# STM32.net
KiCad netlist of a schematic drawn in Altium Designer
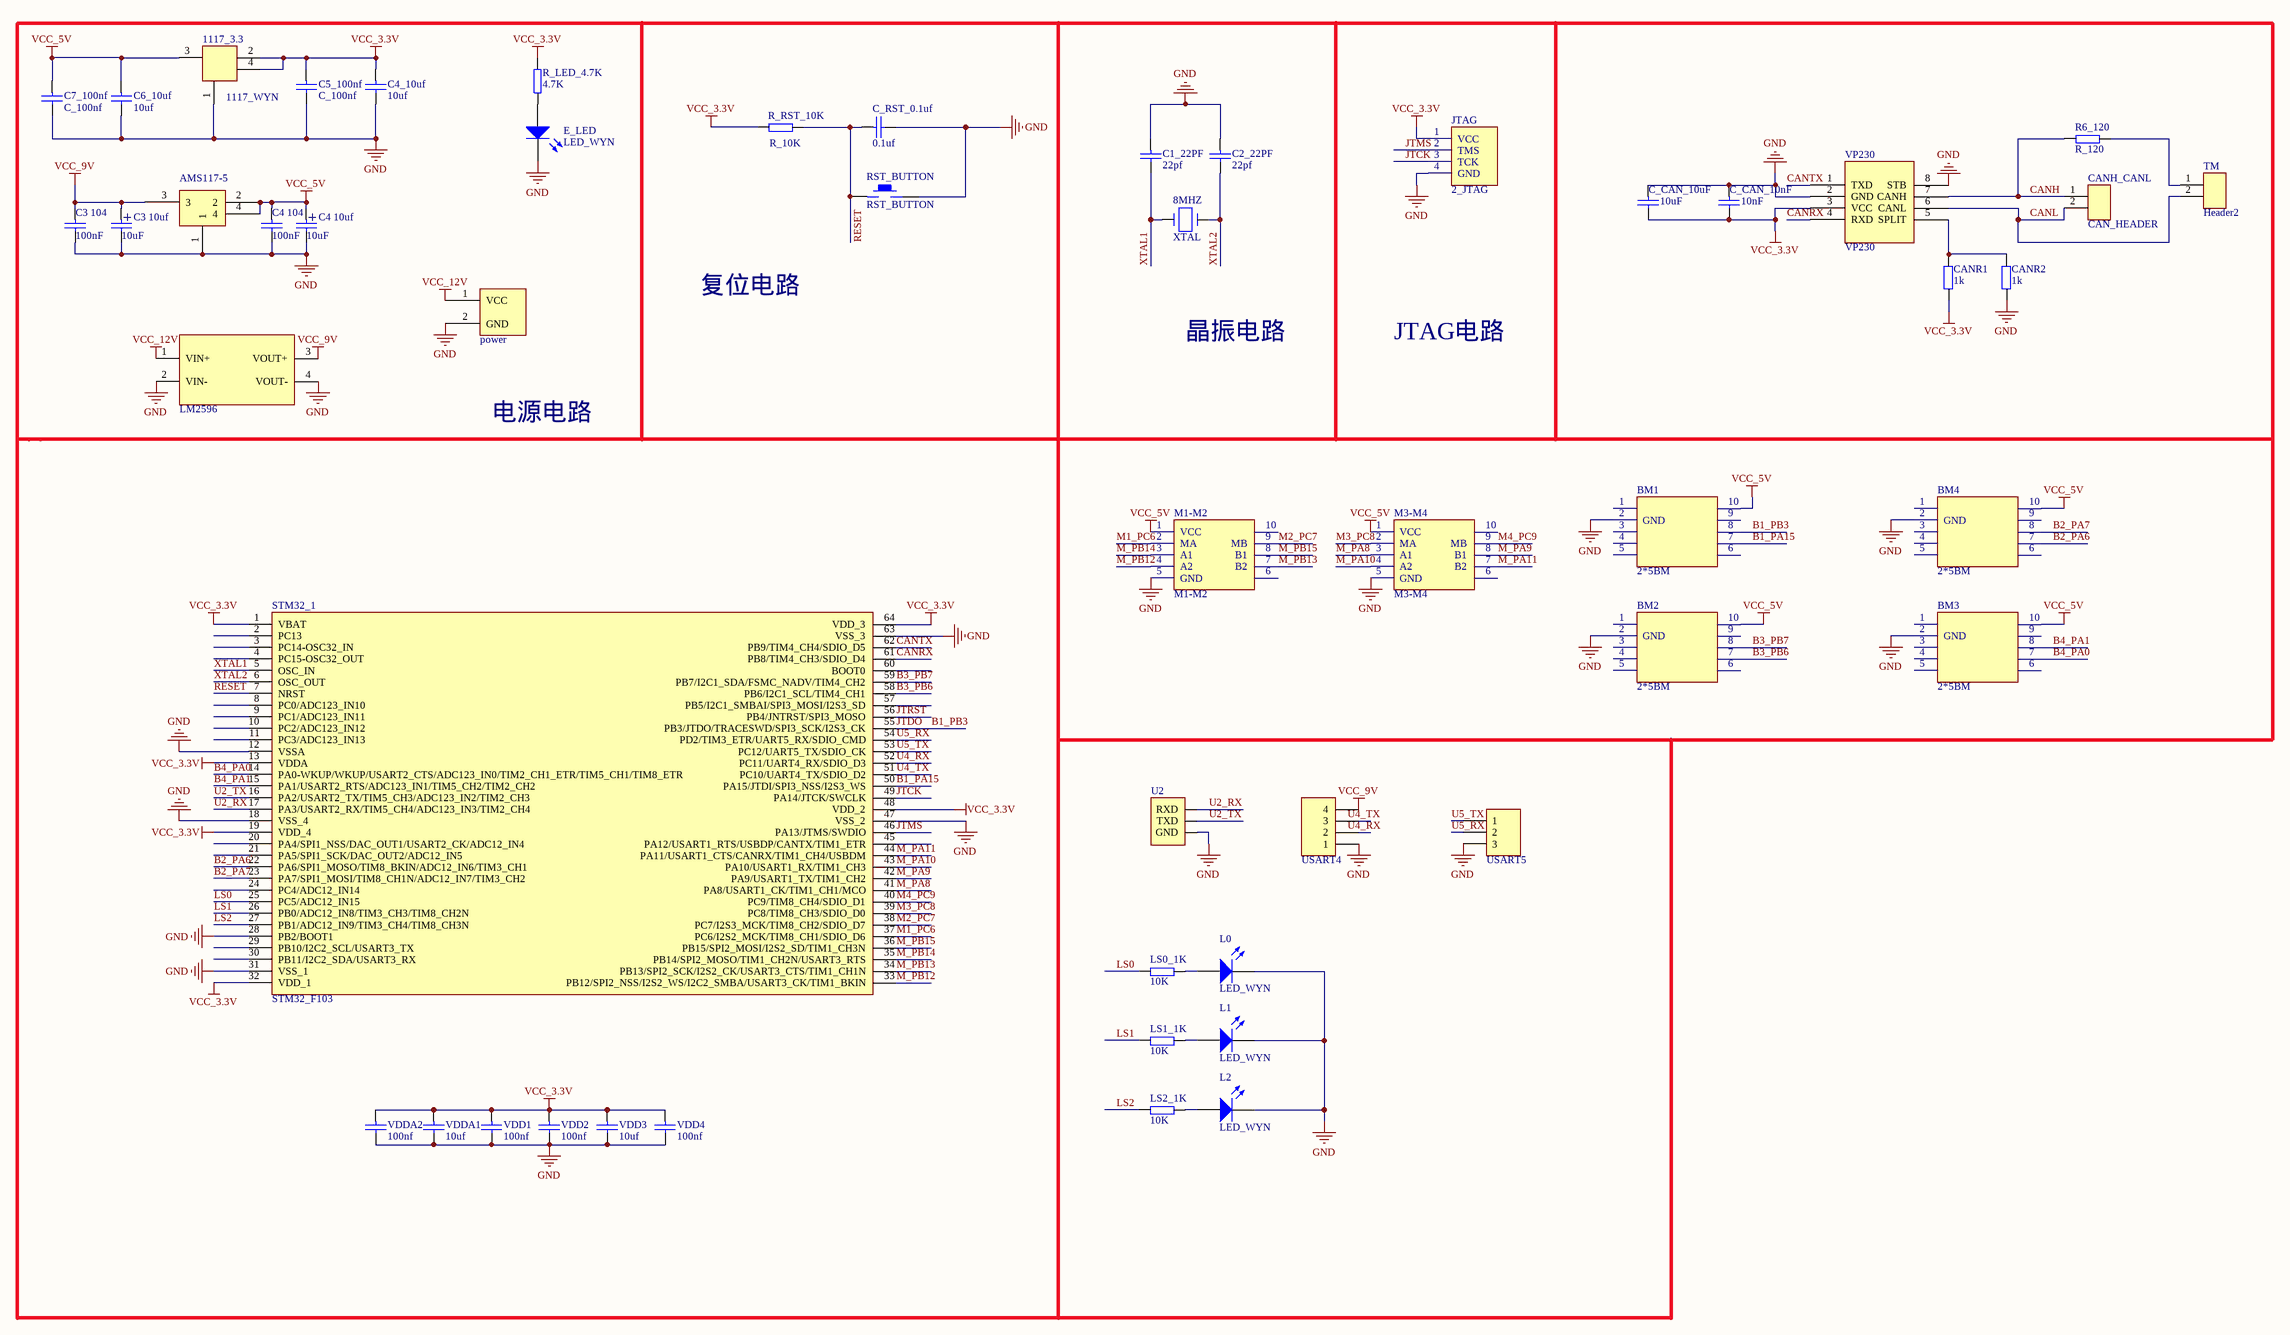
[diagram p0: STM32电机.SchDoc]

(export (version "E")
  (design (tool "Eeschema 10.0.6"))
  (components
    (comp (ref "8MHZ") (value "XTAL") (footprint "XTAL_D") (libsource (lib "STM32主处理板") (part "XTAL")))
    (comp (ref "1117_3.3")
      (value "1117_WYN")
      (footprint "SOT-223_WYN")
      (libsource (lib "STM32主处理板") (part "1117_WYN"))
    )
    (comp (ref "AMS117-5")
      (value "1117-3.3")
      (footprint "SOT-223_WYN")
      (libsource (lib "main") (part "1117_WYN"))
    )
    (comp (ref "BM1") (value "2*5BM") (footprint "JTAG_10to20") (libsource (lib "STM32主处理板") (part "2*5BM")))
    (comp (ref "BM2") (value "2*5BM") (footprint "JTAG_10to20") (libsource (lib "STM32主处理板") (part "2*5BM")))
    (comp (ref "BM3") (value "2*5BM") (footprint "JTAG_10to20") (libsource (lib "STM32主处理板") (part "2*5BM")))
    (comp (ref "BM4") (value "2*5BM") (footprint "JTAG_10to20") (libsource (lib "STM32主处理板") (part "2*5BM")))
    (comp (ref "C1_22PF")
      (value "22pf")
      (footprint "0603_WYH")
      (libsource (lib "STM32主处理板") (part "CAP_WYN"))
    )
    (comp (ref "C2_22PF")
      (value "22pf")
      (footprint "0603_WYH")
      (libsource (lib "STM32主处理板") (part "CAP_WYN"))
    )
    (comp (ref "C3 10uf") (value "10uF") (footprint "0603_WYH") (libsource (lib "main") (part "CAP_POL_WYN")))
    (comp (ref "C3 104") (value "100nF") (footprint "0603_WYH") (libsource (lib "main") (part "CAP_WYN")))
    (comp (ref "C4 10uf") (value "10uF") (footprint "0603_WYH") (libsource (lib "main") (part "CAP_POL_WYN")))
    (comp (ref "C4 104") (value "100nF") (footprint "0603_WYH") (libsource (lib "main") (part "CAP_WYN")))
    (comp (ref "C4_10uf")
      (value "10uf")
      (footprint "0603_WYH")
      (libsource (lib "STM32主处理板") (part "CAP_WYN"))
    )
    (comp (ref "C5_100nf")
      (value "C_100nf")
      (footprint "0603_WYH")
      (libsource (lib "STM32主处理板") (part "CAP_WYN"))
    )
    (comp (ref "C6_10uf")
      (value "10uf")
      (footprint "0603_WYH")
      (libsource (lib "STM32主处理板") (part "CAP_WYN"))
    )
    (comp (ref "C7_100nf")
      (value "C_100nf")
      (footprint "0603_WYH")
      (libsource (lib "STM32主处理板") (part "CAP_WYN"))
    )
    (comp (ref "CANH_CANL")
      (value "CAN_HEADER")
      (footprint "CAN信号")
      (libsource (lib "STM32主处理板") (part "CAN_HEADER"))
    )
    (comp (ref "CANR1") (value "1k") (footprint "0603_WYH") (libsource (lib "战舰STM32开发板底板封装库") (part "R")))
    (comp (ref "CANR2") (value "1k") (footprint "0603_WYH") (libsource (lib "战舰STM32开发板底板封装库") (part "R")))
    (comp (ref "C_CAN_10nF")
      (value "10nF")
      (footprint "0603_WYH")
      (libsource (lib "STM32主处理板") (part "CAP_WYN"))
    )
    (comp (ref "C_CAN_10uF")
      (value "10uF")
      (footprint "0603_WYH")
      (libsource (lib "STM32主处理板") (part "CAP_WYN"))
    )
    (comp (ref "C_RST_0.1uf")
      (value "0.1uf")
      (footprint "0603_WYH")
      (libsource (lib "STM32主处理板") (part "CAP_WYN"))
    )
    (comp (ref "E_LED")
      (value "LED_WYN")
      (footprint "0603_WYH")
      (libsource (lib "STM32主处理板") (part "LED_WYN"))
    )
    (comp (ref "JTAG") (value "2_JTAG") (footprint "2_JTAG") (libsource (lib "STM32主处理板") (part "2_JTAG")))
    (comp (ref "L0") (value "LED_WYN") (footprint "0603_WYH") (libsource (lib "STM32主处理板") (part "LED_WYN")))
    (comp (ref "L1") (value "LED_WYN") (footprint "0603_WYH") (libsource (lib "STM32主处理板") (part "LED_WYN")))
    (comp (ref "L2") (value "LED_WYN") (footprint "0603_WYH") (libsource (lib "STM32主处理板") (part "LED_WYN")))
    (comp (ref "LM2596") (value "LM2596") (footprint "LM2596") (libsource (lib "救援2") (part "LM2596")))
    (comp (ref "LS0_1K") (value "10K") (footprint "0603_WYH") (libsource (lib "战舰STM32开发板底板封装库") (part "R")))
    (comp (ref "LS1_1K") (value "10K") (footprint "0603_WYH") (libsource (lib "战舰STM32开发板底板封装库") (part "R")))
    (comp (ref "LS2_1K") (value "10K") (footprint "0603_WYH") (libsource (lib "战舰STM32开发板底板封装库") (part "R")))
    (comp (ref "M1-M2") (value "M1-M2") (footprint "JTAG_10to20") (libsource (lib "STM32主处理板") (part "电机接口")))
    (comp (ref "M3-M4") (value "M3-M4") (footprint "JTAG_10to20") (libsource (lib "STM32主处理板") (part "电机接口")))
    (comp (ref "POWER") (value "power") (footprint "power") (libsource (lib "救援1") (part "power")))
    (comp (ref "R6_120")
      (value "R_120")
      (footprint "0603_WYH")
      (libsource (lib "战舰STM32开发板底板封装库") (part "R"))
    )
    (comp (ref "RST_BUTTON")
      (value "RST_BUTTON")
      (footprint "CLCK")
      (libsource (lib "STM32主处理板") (part "RST_BUTTON"))
    )
    (comp (ref "R_LED_4.7K")
      (value "4.7K")
      (footprint "0603_WYH")
      (libsource (lib "STM32主处理板") (part "RES_WYN"))
    )
    (comp (ref "R_RST_10K")
      (value "R_10K")
      (footprint "0603_WYH")
      (libsource (lib "战舰STM32开发板底板封装库") (part "R"))
    )
    (comp (ref "STM32_1")
      (value "STM32_F103")
      (footprint "STM32TSQFP50P1200X1200X160-64N")
      (libsource (lib "STM32主处理板") (part "STM32_F103"))
    )
    (comp (ref "TM") (value "Header2") (footprint "HDR1X2") (libsource (lib "STM32主处理板") (part "Header2")))
    (comp (ref "U2") (value "三针串口") (footprint "HDR1X3") (libsource (lib "STM32主处理板") (part "三针串口")))
    (comp (ref "USART4") (value "Header-4") (footprint "HDR1X4") (libsource (lib "救援1") (part "Header-4")))
    (comp (ref "USART5") (value "Header-3") (footprint "HDR1X3") (libsource (lib "救援1") (part "Header-3")))
    (comp (ref "VDD1") (value "100nf") (footprint "0603_WYH") (libsource (lib "STM32主处理板") (part "CAP_WYN")))
    (comp (ref "VDD2") (value "100nf") (footprint "0603_WYH") (libsource (lib "STM32主处理板") (part "CAP_WYN")))
    (comp (ref "VDD3") (value "10uf") (footprint "0603_WYH") (libsource (lib "STM32主处理板") (part "CAP_WYN")))
    (comp (ref "VDD4") (value "100nf") (footprint "0603_WYH") (libsource (lib "STM32主处理板") (part "CAP_WYN")))
    (comp (ref "VDDA1") (value "10uf") (footprint "0603_WYH") (libsource (lib "STM32主处理板") (part "CAP_WYN")))
    (comp (ref "VDDA2") (value "100nf") (footprint "0603_WYH") (libsource (lib "STM32主处理板") (part "CAP_WYN")))
    (comp (ref "VP230") (value "VP230") (footprint "VP230") (libsource (lib "STM32主处理板") (part "VP230")))
  )
  (nets
    (net (code "1") (name "/B1_PA15") (class "Default")
      (node (ref "BM1") (pin "7") (pintype "passive"))
      (node (ref "STM32_1") (pin "50") (pinfunction "PA15/JTDI/SPI3_NSS/I2S3_WS_50") (pintype "passive"))
    )
    (net (code "2") (name "/B1_PB3") (class "Default")
      (node (ref "BM1") (pin "8") (pintype "passive"))
      (node (ref "STM32_1") (pin "55") (pinfunction "PB3/JTDO/TRACESWD/SPI3_SCK/I2S3_CK_55") (pintype "passive"))
    )
    (net (code "3") (name "/B2_PA6") (class "Default")
      (node (ref "BM4") (pin "7") (pintype "passive"))
      (node (ref "STM32_1") (pin "22") (pinfunction "PA6/SPI1_MOSO/TIM8_BKIN/ADC12_IN6/TIM3_CH1_22") (pintype "passive"))
    )
    (net (code "4") (name "/B2_PA7") (class "Default")
      (node (ref "BM4") (pin "8") (pintype "passive"))
      (node (ref "STM32_1") (pin "23") (pinfunction "PA7/SPI1_MOSI/TIM8_CH1N/ADC12_IN7/TIM3_CH2_23") (pintype "passive"))
    )
    (net (code "5") (name "/B3_PB6") (class "Default")
      (node (ref "BM2") (pin "7") (pintype "passive"))
      (node (ref "STM32_1") (pin "58") (pinfunction "PB6/I2C1_SCL/TIM4_CH1_58") (pintype "passive"))
    )
    (net (code "6") (name "/B3_PB7") (class "Default")
      (node (ref "BM2") (pin "8") (pintype "passive"))
      (node (ref "STM32_1") (pin "59") (pinfunction "PB7/I2C1_SDA/FSMC_NADV/TIM4_CH2_59") (pintype "passive"))
    )
    (net (code "7") (name "/B4_PA0") (class "Default")
      (node (ref "BM3") (pin "7") (pintype "passive"))
      (node (ref "STM32_1") (pin "14") (pinfunction "PA0-WKUP/WKUP/USART2_CTS/ADC123_IN0/TIM2_CH1_ETR/TIM5_CH1/TIM8_ETR_14") (pintype "passive"))
    )
    (net (code "8") (name "/B4_PA1") (class "Default")
      (node (ref "BM3") (pin "8") (pintype "passive"))
      (node (ref "STM32_1") (pin "15") (pinfunction "PA1/USART2_RTS/ADC123_IN1/TIM5_CH2/TIM2_CH2_15") (pintype "passive"))
    )
    (net (code "9") (name "/CANH") (class "Default")
      (node (ref "CANH_CANL") (pin "1") (pintype "passive"))
      (node (ref "R6_120") (pin "1") (pintype "passive"))
      (node (ref "VP230") (pin "7") (pinfunction "CANH_7") (pintype "passive"))
    )
    (net (code "10") (name "/CANL") (class "Default")
      (node (ref "CANH_CANL") (pin "2") (pintype "passive"))
      (node (ref "TM") (pin "2") (pintype "passive"))
      (node (ref "VP230") (pin "6") (pinfunction "CANL_6") (pintype "passive"))
    )
    (net (code "11") (name "/CANRX") (class "Default")
      (node (ref "STM32_1") (pin "61") (pinfunction "PB8/TIM4_CH3/SDIO_D4_61") (pintype "passive"))
      (node (ref "VP230") (pin "4") (pinfunction "RXD_4") (pintype "passive"))
    )
    (net (code "12") (name "/CANTX") (class "Default")
      (node (ref "STM32_1") (pin "62") (pinfunction "PB9/TIM4_CH4/SDIO_D5_62") (pintype "passive"))
      (node (ref "VP230") (pin "1") (pinfunction "TXD_1") (pintype "passive"))
    )
    (net (code "13") (name "/JTCK") (class "Default")
      (node (ref "JTAG") (pin "3") (pinfunction "TCK_3") (pintype "passive"))
      (node (ref "STM32_1") (pin "49") (pinfunction "PA14/JTCK/SWCLK_49") (pintype "passive"))
    )
    (net (code "14") (name "/JTMS") (class "Default")
      (node (ref "JTAG") (pin "2") (pinfunction "TMS_2") (pintype "passive"))
      (node (ref "STM32_1") (pin "46") (pinfunction "PA13/JTMS/SWDIO_46") (pintype "passive"))
    )
    (net (code "15") (name "/JTRST") (class "Default")
      (node (ref "STM32_1") (pin "56") (pinfunction "PB4/JNTRST/SPI3_MOSO_56") (pintype "passive"))
    )
    (net (code "16") (name "/LS0") (class "Default")
      (node (ref "LS0_1K") (pin "1") (pintype "passive"))
      (node (ref "STM32_1") (pin "25") (pinfunction "PC5/ADC12_IN15_25") (pintype "passive"))
    )
    (net (code "17") (name "/LS1") (class "Default")
      (node (ref "LS1_1K") (pin "1") (pintype "passive"))
      (node (ref "STM32_1") (pin "26") (pinfunction "PB0/ADC12_IN8/TIM3_CH3/TIM8_CH2N_26") (pintype "passive"))
    )
    (net (code "18") (name "/LS2") (class "Default")
      (node (ref "LS2_1K") (pin "1") (pintype "passive"))
      (node (ref "STM32_1") (pin "27") (pinfunction "PB1/ADC12_IN9/TIM3_CH4/TIM8_CH3N_27") (pintype "passive"))
    )
    (net (code "19") (name "/M1_PC6") (class "Default")
      (node (ref "M1-M2") (pin "2") (pinfunction "MA_2") (pintype "passive"))
      (node (ref "STM32_1") (pin "37") (pinfunction "PC6/I2S2_MCK/TIM8_CH1/SDIO_D6_37") (pintype "passive"))
    )
    (net (code "20") (name "/M2_PC7") (class "Default")
      (node (ref "M1-M2") (pin "9") (pinfunction "MB_9") (pintype "passive"))
      (node (ref "STM32_1") (pin "38") (pinfunction "PC7/I2S3_MCK/TIM8_CH2/SDIO_D7_38") (pintype "passive"))
    )
    (net (code "21") (name "/M3_PC8") (class "Default")
      (node (ref "M3-M4") (pin "2") (pinfunction "MA_2") (pintype "passive"))
      (node (ref "STM32_1") (pin "39") (pinfunction "PC8/TIM8_CH3/SDIO_D0_39") (pintype "passive"))
    )
    (net (code "22") (name "/M4_PC9") (class "Default")
      (node (ref "M3-M4") (pin "9") (pinfunction "MB_9") (pintype "passive"))
      (node (ref "STM32_1") (pin "40") (pinfunction "PC9/TIM8_CH4/SDIO_D1_40") (pintype "passive"))
    )
    (net (code "23") (name "/M_PA8") (class "Default")
      (node (ref "M3-M4") (pin "3") (pinfunction "A1_3") (pintype "passive"))
      (node (ref "STM32_1") (pin "41") (pinfunction "PA8/USART1_CK/TIM1_CH1/MCO_41") (pintype "passive"))
    )
    (net (code "24") (name "/M_PA9") (class "Default")
      (node (ref "M3-M4") (pin "8") (pinfunction "B1_8") (pintype "passive"))
      (node (ref "STM32_1") (pin "42") (pinfunction "PA9/USART1_TX/TIM1_CH2_42") (pintype "passive"))
    )
    (net (code "25") (name "/M_PA10") (class "Default")
      (node (ref "M3-M4") (pin "4") (pinfunction "A2_4") (pintype "passive"))
      (node (ref "STM32_1") (pin "43") (pinfunction "PA10/USART1_RX/TIM1_CH3_43") (pintype "passive"))
    )
    (net (code "26") (name "/M_PA11") (class "Default")
      (node (ref "M3-M4") (pin "7") (pinfunction "B2_7") (pintype "passive"))
      (node (ref "STM32_1") (pin "44") (pinfunction "PA11/USART1_CTS/CANRX/TIM1_CH4/USBDM_44") (pintype "passive"))
    )
    (net (code "27") (name "/M_PB12") (class "Default")
      (node (ref "M1-M2") (pin "4") (pinfunction "A2_4") (pintype "passive"))
      (node (ref "STM32_1") (pin "33") (pinfunction "PB12/SPI2_NSS/I2S2_WS/I2C2_SMBA/USART3_CK/TIM1_BKIN_33") (pintype "passive"))
    )
    (net (code "28") (name "/M_PB13") (class "Default")
      (node (ref "M1-M2") (pin "7") (pinfunction "B2_7") (pintype "passive"))
      (node (ref "STM32_1") (pin "34") (pinfunction "PB13/SPI2_SCK/I2S2_CK/USART3_CTS/TIM1_CH1N_34") (pintype "passive"))
    )
    (net (code "29") (name "/M_PB14") (class "Default")
      (node (ref "M1-M2") (pin "3") (pinfunction "A1_3") (pintype "passive"))
      (node (ref "STM32_1") (pin "35") (pinfunction "PB14/SPI2_MOSO/TIM1_CH2N/USART3_RTS_35") (pintype "passive"))
    )
    (net (code "30") (name "/M_PB15") (class "Default")
      (node (ref "M1-M2") (pin "8") (pinfunction "B1_8") (pintype "passive"))
      (node (ref "STM32_1") (pin "36") (pinfunction "PB15/SPI2_MOSI/I2S2_SD/TIM1_CH3N_36") (pintype "passive"))
    )
    (net (code "31") (name "/RESET") (class "Default")
      (node (ref "C_RST_0.1uf") (pin "1") (pintype "passive"))
      (node (ref "RST_BUTTON") (pin "1") (pinfunction "1_1") (pintype "passive"))
      (node (ref "R_RST_10K") (pin "2") (pintype "passive"))
      (node (ref "STM32_1") (pin "7") (pinfunction "NRST_7") (pintype "passive"))
    )
    (net (code "32") (name "/U2_RX") (class "Default")
      (node (ref "STM32_1") (pin "17") (pinfunction "PA3/USART2_RX/TIM5_CH4/ADC123_IN3/TIM2_CH4_17") (pintype "passive"))
      (node (ref "U2") (pin "1") (pinfunction "RXD_1") (pintype "passive"))
    )
    (net (code "33") (name "/U2_TX") (class "Default")
      (node (ref "STM32_1") (pin "16") (pinfunction "PA2/USART2_TX/TIM5_CH3/ADC123_IN2/TIM2_CH3_16") (pintype "passive"))
      (node (ref "U2") (pin "2") (pinfunction "TXD_2") (pintype "passive"))
    )
    (net (code "34") (name "/U4_RX") (class "Default")
      (node (ref "STM32_1") (pin "52") (pinfunction "PC11/UART4_RX/SDIO_D3_52") (pintype "passive"))
    )
    (net (code "35") (name "/U4_TX") (class "Default")
      (node (ref "STM32_1") (pin "51") (pinfunction "PC10/UART4_TX/SDIO_D2_51") (pintype "passive"))
    )
    (net (code "36") (name "/U5_RX") (class "Default")
      (node (ref "STM32_1") (pin "54") (pinfunction "PD2/TIM3_ETR/UART5_RX/SDIO_CMD_54") (pintype "passive"))
      (node (ref "USART5") (pin "2") (pinfunction "2_2") (pintype "passive"))
    )
    (net (code "37") (name "/U5_TX") (class "Default")
      (node (ref "STM32_1") (pin "53") (pinfunction "PC12/UART5_TX/SDIO_CK_53") (pintype "passive"))
      (node (ref "USART5") (pin "1") (pinfunction "1_1") (pintype "passive"))
    )
    (net (code "38") (name "/XTAL1") (class "Default")
      (node (ref "8MHZ") (pin "1") (pinfunction "1_1") (pintype "passive"))
      (node (ref "C1_22PF") (pin "2") (pintype "passive"))
      (node (ref "STM32_1") (pin "5") (pinfunction "OSC_IN_5") (pintype "passive"))
    )
    (net (code "39") (name "/XTAL2") (class "Default")
      (node (ref "8MHZ") (pin "2") (pinfunction "2_2") (pintype "passive"))
      (node (ref "C2_22PF") (pin "2") (pintype "passive"))
      (node (ref "STM32_1") (pin "6") (pinfunction "OSC_OUT_6") (pintype "passive"))
    )
    (net (code "40") (name "GND") (class "Default")
      (node (ref "1117_3.3") (pin "1") (pintype "passive"))
      (node (ref "AMS117-5") (pin "1") (pinfunction "1_1") (pintype "passive"))
      (node (ref "BM1") (pin "2") (pinfunction "GND_2") (pintype "passive"))
      (node (ref "BM2") (pin "2") (pinfunction "GND_2") (pintype "passive"))
      (node (ref "BM3") (pin "2") (pinfunction "GND_2") (pintype "passive"))
      (node (ref "BM4") (pin "2") (pinfunction "GND_2") (pintype "passive"))
      (node (ref "C1_22PF") (pin "1") (pintype "passive"))
      (node (ref "C2_22PF") (pin "1") (pintype "passive"))
      (node (ref "C3 104") (pin "2") (pintype "passive"))
      (node (ref "C3 10uf") (pin "2") (pintype "passive"))
      (node (ref "C4 104") (pin "2") (pintype "passive"))
      (node (ref "C4 10uf") (pin "2") (pintype "passive"))
      (node (ref "C4_10uf") (pin "2") (pintype "passive"))
      (node (ref "C5_100nf") (pin "2") (pintype "passive"))
      (node (ref "C6_10uf") (pin "2") (pintype "passive"))
      (node (ref "C7_100nf") (pin "2") (pintype "passive"))
      (node (ref "CANR2") (pin "2") (pintype "passive"))
      (node (ref "C_CAN_10nF") (pin "1") (pintype "passive"))
      (node (ref "C_CAN_10uF") (pin "1") (pintype "passive"))
      (node (ref "C_RST_0.1uf") (pin "2") (pintype "passive"))
      (node (ref "E_LED") (pin "2") (pinfunction "K_2") (pintype "passive"))
      (node (ref "JTAG") (pin "4") (pinfunction "GND_4") (pintype "passive"))
      (node (ref "L0") (pin "2") (pinfunction "K_2") (pintype "passive"))
      (node (ref "L1") (pin "2") (pinfunction "K_2") (pintype "passive"))
      (node (ref "L2") (pin "2") (pinfunction "K_2") (pintype "passive"))
      (node (ref "LM2596") (pin "2") (pinfunction "VIN-_2") (pintype "passive"))
      (node (ref "LM2596") (pin "4") (pinfunction "VOUT-_4") (pintype "passive"))
      (node (ref "M1-M2") (pin "5") (pinfunction "GND_5") (pintype "passive"))
      (node (ref "M3-M4") (pin "5") (pinfunction "GND_5") (pintype "passive"))
      (node (ref "POWER") (pin "2") (pinfunction "GND_2") (pintype "passive"))
      (node (ref "RST_BUTTON") (pin "2") (pinfunction "2_2") (pintype "passive"))
      (node (ref "STM32_1") (pin "12") (pinfunction "VSSA_12") (pintype "passive"))
      (node (ref "STM32_1") (pin "18") (pinfunction "VSS_4_18") (pintype "passive"))
      (node (ref "STM32_1") (pin "28") (pinfunction "PB2/BOOT1_28") (pintype "passive"))
      (node (ref "STM32_1") (pin "31") (pinfunction "VSS_1_31") (pintype "passive"))
      (node (ref "STM32_1") (pin "47") (pinfunction "VSS_2_47") (pintype "passive"))
      (node (ref "STM32_1") (pin "63") (pinfunction "VSS_3_63") (pintype "passive"))
      (node (ref "U2") (pin "3") (pinfunction "GND_3") (pintype "passive"))
      (node (ref "USART4") (pin "1") (pinfunction "1_1") (pintype "passive"))
      (node (ref "USART5") (pin "3") (pinfunction "3_3") (pintype "passive"))
      (node (ref "VDD1") (pin "2") (pintype "passive"))
      (node (ref "VDD2") (pin "2") (pintype "passive"))
      (node (ref "VDD3") (pin "2") (pintype "passive"))
      (node (ref "VDD4") (pin "2") (pintype "passive"))
      (node (ref "VDDA1") (pin "2") (pintype "passive"))
      (node (ref "VDDA2") (pin "2") (pintype "passive"))
      (node (ref "VP230") (pin "2") (pinfunction "GND_2") (pintype "passive"))
      (node (ref "VP230") (pin "8") (pinfunction "STB_8") (pintype "passive"))
    )
    (net (code "41") (name "Net-(E_LED-A)") (class "Default")
      (node (ref "E_LED") (pin "1") (pinfunction "A_1") (pintype "passive"))
      (node (ref "R_LED_4.7K") (pin "1") (pinfunction "1_1") (pintype "passive"))
    )
    (net (code "42") (name "Net-(L0-A)") (class "Default")
      (node (ref "L0") (pin "1") (pinfunction "A_1") (pintype "passive"))
      (node (ref "LS0_1K") (pin "2") (pintype "passive"))
    )
    (net (code "43") (name "Net-(L1-A)") (class "Default")
      (node (ref "L1") (pin "1") (pinfunction "A_1") (pintype "passive"))
      (node (ref "LS1_1K") (pin "2") (pintype "passive"))
    )
    (net (code "44") (name "Net-(L2-A)") (class "Default")
      (node (ref "L2") (pin "1") (pinfunction "A_1") (pintype "passive"))
      (node (ref "LS2_1K") (pin "2") (pintype "passive"))
    )
    (net (code "45") (name "Net-(R6_120-Pad2)") (class "Default")
      (node (ref "R6_120") (pin "2") (pintype "passive"))
      (node (ref "TM") (pin "1") (pintype "passive"))
    )
    (net (code "46") (name "Net-(VP230-SPLIT)") (class "Default")
      (node (ref "CANR1") (pin "1") (pintype "passive"))
      (node (ref "CANR2") (pin "1") (pintype "passive"))
      (node (ref "VP230") (pin "5") (pinfunction "SPLIT_5") (pintype "passive"))
    )
    (net (code "47") (name "VCC_3.3V") (class "Default")
      (node (ref "1117_3.3") (pin "2") (pintype "passive"))
      (node (ref "1117_3.3") (pin "4") (pintype "passive"))
      (node (ref "C4_10uf") (pin "1") (pintype "passive"))
      (node (ref "C5_100nf") (pin "1") (pintype "passive"))
      (node (ref "CANR1") (pin "2") (pintype "passive"))
      (node (ref "C_CAN_10nF") (pin "2") (pintype "passive"))
      (node (ref "C_CAN_10uF") (pin "2") (pintype "passive"))
      (node (ref "JTAG") (pin "1") (pinfunction "VCC_1") (pintype "passive"))
      (node (ref "R_LED_4.7K") (pin "2") (pinfunction "2_2") (pintype "passive"))
      (node (ref "R_RST_10K") (pin "1") (pintype "passive"))
      (node (ref "STM32_1") (pin "1") (pinfunction "VBAT_1") (pintype "passive"))
      (node (ref "STM32_1") (pin "13") (pinfunction "VDDA_13") (pintype "passive"))
      (node (ref "STM32_1") (pin "19") (pinfunction "VDD_4_19") (pintype "passive"))
      (node (ref "STM32_1") (pin "32") (pinfunction "VDD_1_32") (pintype "passive"))
      (node (ref "STM32_1") (pin "48") (pinfunction "VDD_2_48") (pintype "passive"))
      (node (ref "STM32_1") (pin "64") (pinfunction "VDD_3_64") (pintype "passive"))
      (node (ref "VDD1") (pin "1") (pintype "passive"))
      (node (ref "VDD2") (pin "1") (pintype "passive"))
      (node (ref "VDD3") (pin "1") (pintype "passive"))
      (node (ref "VDD4") (pin "1") (pintype "passive"))
      (node (ref "VDDA1") (pin "1") (pintype "passive"))
      (node (ref "VDDA2") (pin "1") (pintype "passive"))
      (node (ref "VP230") (pin "3") (pinfunction "VCC_3") (pintype "passive"))
    )
    (net (code "48") (name "VCC_5V") (class "Default")
      (node (ref "1117_3.3") (pin "3") (pintype "passive"))
      (node (ref "AMS117-5") (pin "2") (pinfunction "2_2") (pintype "passive"))
      (node (ref "AMS117-5") (pin "4") (pinfunction "4_4") (pintype "passive"))
      (node (ref "BM1") (pin "10") (pintype "passive"))
      (node (ref "BM2") (pin "10") (pintype "passive"))
      (node (ref "BM3") (pin "10") (pintype "passive"))
      (node (ref "BM4") (pin "10") (pintype "passive"))
      (node (ref "C4 104") (pin "1") (pintype "passive"))
      (node (ref "C4 10uf") (pin "1") (pintype "passive"))
      (node (ref "C6_10uf") (pin "1") (pintype "passive"))
      (node (ref "C7_100nf") (pin "1") (pintype "passive"))
      (node (ref "M1-M2") (pin "1") (pinfunction "VCC_1") (pintype "passive"))
      (node (ref "M3-M4") (pin "1") (pinfunction "VCC_1") (pintype "passive"))
    )
    (net (code "49") (name "VCC_9V") (class "Default")
      (node (ref "AMS117-5") (pin "3") (pinfunction "3_3") (pintype "passive"))
      (node (ref "C3 104") (pin "1") (pintype "passive"))
      (node (ref "C3 10uf") (pin "1") (pintype "passive"))
      (node (ref "LM2596") (pin "3") (pinfunction "VOUT+_3") (pintype "passive"))
      (node (ref "USART4") (pin "4") (pinfunction "4_4") (pintype "passive"))
    )
    (net (code "50") (name "VCC_12V") (class "Default")
      (node (ref "LM2596") (pin "1") (pinfunction "VIN+_1") (pintype "passive"))
      (node (ref "POWER") (pin "1") (pinfunction "VCC_1") (pintype "passive"))
    )
    (net (code "51") (name "unconnected-(BM1-Pad1)") (class "Default")
      (node (ref "BM1") (pin "1") (pintype "passive"))
    )
    (net (code "52") (name "unconnected-(BM1-Pad3)") (class "Default")
      (node (ref "BM1") (pin "3") (pintype "passive"))
    )
    (net (code "53") (name "unconnected-(BM1-Pad4)") (class "Default")
      (node (ref "BM1") (pin "4") (pintype "passive"))
    )
    (net (code "54") (name "unconnected-(BM1-Pad5)") (class "Default")
      (node (ref "BM1") (pin "5") (pintype "passive"))
    )
    (net (code "55") (name "unconnected-(BM1-Pad6)") (class "Default")
      (node (ref "BM1") (pin "6") (pintype "passive"))
    )
    (net (code "56") (name "unconnected-(BM1-Pad9)") (class "Default")
      (node (ref "BM1") (pin "9") (pintype "passive"))
    )
    (net (code "57") (name "unconnected-(BM2-Pad1)") (class "Default")
      (node (ref "BM2") (pin "1") (pintype "passive"))
    )
    (net (code "58") (name "unconnected-(BM2-Pad3)") (class "Default")
      (node (ref "BM2") (pin "3") (pintype "passive"))
    )
    (net (code "59") (name "unconnected-(BM2-Pad4)") (class "Default")
      (node (ref "BM2") (pin "4") (pintype "passive"))
    )
    (net (code "60") (name "unconnected-(BM2-Pad5)") (class "Default")
      (node (ref "BM2") (pin "5") (pintype "passive"))
    )
    (net (code "61") (name "unconnected-(BM2-Pad6)") (class "Default")
      (node (ref "BM2") (pin "6") (pintype "passive"))
    )
    (net (code "62") (name "unconnected-(BM2-Pad9)") (class "Default")
      (node (ref "BM2") (pin "9") (pintype "passive"))
    )
    (net (code "63") (name "unconnected-(BM3-Pad1)") (class "Default")
      (node (ref "BM3") (pin "1") (pintype "passive"))
    )
    (net (code "64") (name "unconnected-(BM3-Pad3)") (class "Default")
      (node (ref "BM3") (pin "3") (pintype "passive"))
    )
    (net (code "65") (name "unconnected-(BM3-Pad4)") (class "Default")
      (node (ref "BM3") (pin "4") (pintype "passive"))
    )
    (net (code "66") (name "unconnected-(BM3-Pad5)") (class "Default")
      (node (ref "BM3") (pin "5") (pintype "passive"))
    )
    (net (code "67") (name "unconnected-(BM3-Pad6)") (class "Default")
      (node (ref "BM3") (pin "6") (pintype "passive"))
    )
    (net (code "68") (name "unconnected-(BM3-Pad9)") (class "Default")
      (node (ref "BM3") (pin "9") (pintype "passive"))
    )
    (net (code "69") (name "unconnected-(BM4-Pad1)") (class "Default")
      (node (ref "BM4") (pin "1") (pintype "passive"))
    )
    (net (code "70") (name "unconnected-(BM4-Pad3)") (class "Default")
      (node (ref "BM4") (pin "3") (pintype "passive"))
    )
    (net (code "71") (name "unconnected-(BM4-Pad4)") (class "Default")
      (node (ref "BM4") (pin "4") (pintype "passive"))
    )
    (net (code "72") (name "unconnected-(BM4-Pad5)") (class "Default")
      (node (ref "BM4") (pin "5") (pintype "passive"))
    )
    (net (code "73") (name "unconnected-(BM4-Pad6)") (class "Default")
      (node (ref "BM4") (pin "6") (pintype "passive"))
    )
    (net (code "74") (name "unconnected-(BM4-Pad9)") (class "Default")
      (node (ref "BM4") (pin "9") (pintype "passive"))
    )
    (net (code "75") (name "unconnected-(M1-M2-Pad6)") (class "Default")
      (node (ref "M1-M2") (pin "6") (pintype "passive"))
    )
    (net (code "76") (name "unconnected-(M1-M2-Pad10)") (class "Default")
      (node (ref "M1-M2") (pin "10") (pintype "passive"))
    )
    (net (code "77") (name "unconnected-(M3-M4-Pad6)") (class "Default")
      (node (ref "M3-M4") (pin "6") (pintype "passive"))
    )
    (net (code "78") (name "unconnected-(M3-M4-Pad10)") (class "Default")
      (node (ref "M3-M4") (pin "10") (pintype "passive"))
    )
    (net (code "79") (name "unconnected-(STM32_1-BOOT0-Pad60)") (class "Default")
      (node (ref "STM32_1") (pin "60") (pinfunction "BOOT0_60") (pintype "passive"))
    )
    (net (code "80") (name "unconnected-(STM32_1-PA4{slash}SPI1_NSS{slash}DAC_OUT1{slash}USART2_CK{slash}ADC12_IN4-Pad20)") (class "Default")
      (node (ref "STM32_1") (pin "20") (pinfunction "PA4/SPI1_NSS/DAC_OUT1/USART2_CK/ADC12_IN4_20") (pintype "passive"))
    )
    (net (code "81") (name "unconnected-(STM32_1-PA5{slash}SPI1_SCK{slash}DAC_OUT2{slash}ADC12_IN5-Pad21)") (class "Default")
      (node (ref "STM32_1") (pin "21") (pinfunction "PA5/SPI1_SCK/DAC_OUT2/ADC12_IN5_21") (pintype "passive"))
    )
    (net (code "82") (name "unconnected-(STM32_1-PA12{slash}USART1_RTS{slash}USBDP{slash}CANTX{slash}TIM1_ETR-Pad45)") (class "Default")
      (node (ref "STM32_1") (pin "45") (pinfunction "PA12/USART1_RTS/USBDP/CANTX/TIM1_ETR_45") (pintype "passive"))
    )
    (net (code "83") (name "unconnected-(STM32_1-PB5{slash}I2C1_SMBAI{slash}SPI3_MOSI{slash}I2S3_SD-Pad57)") (class "Default")
      (node (ref "STM32_1") (pin "57") (pinfunction "PB5/I2C1_SMBAI/SPI3_MOSI/I2S3_SD_57") (pintype "passive"))
    )
    (net (code "84") (name "unconnected-(STM32_1-PB10{slash}I2C2_SCL{slash}USART3_TX-Pad29)") (class "Default")
      (node (ref "STM32_1") (pin "29") (pinfunction "PB10/I2C2_SCL/USART3_TX_29") (pintype "passive"))
    )
    (net (code "85") (name "unconnected-(STM32_1-PB11{slash}I2C2_SDA{slash}USART3_RX-Pad30)") (class "Default")
      (node (ref "STM32_1") (pin "30") (pinfunction "PB11/I2C2_SDA/USART3_RX_30") (pintype "passive"))
    )
    (net (code "86") (name "unconnected-(STM32_1-PC0{slash}ADC123_IN10-Pad8)") (class "Default")
      (node (ref "STM32_1") (pin "8") (pinfunction "PC0/ADC123_IN10_8") (pintype "passive"))
    )
    (net (code "87") (name "unconnected-(STM32_1-PC1{slash}ADC123_IN11-Pad9)") (class "Default")
      (node (ref "STM32_1") (pin "9") (pinfunction "PC1/ADC123_IN11_9") (pintype "passive"))
    )
    (net (code "88") (name "unconnected-(STM32_1-PC2{slash}ADC123_IN12-Pad10)") (class "Default")
      (node (ref "STM32_1") (pin "10") (pinfunction "PC2/ADC123_IN12_10") (pintype "passive"))
    )
    (net (code "89") (name "unconnected-(STM32_1-PC3{slash}ADC123_IN13-Pad11)") (class "Default")
      (node (ref "STM32_1") (pin "11") (pinfunction "PC3/ADC123_IN13_11") (pintype "passive"))
    )
    (net (code "90") (name "unconnected-(STM32_1-PC4{slash}ADC12_IN14-Pad24)") (class "Default")
      (node (ref "STM32_1") (pin "24") (pinfunction "PC4/ADC12_IN14_24") (pintype "passive"))
    )
    (net (code "91") (name "unconnected-(STM32_1-PC13-Pad2)") (class "Default")
      (node (ref "STM32_1") (pin "2") (pinfunction "PC13_2") (pintype "passive"))
    )
    (net (code "92") (name "unconnected-(STM32_1-PC14-OSC32_IN-Pad3)") (class "Default")
      (node (ref "STM32_1") (pin "3") (pinfunction "PC14-OSC32_IN_3") (pintype "passive"))
    )
    (net (code "93") (name "unconnected-(STM32_1-PC15-OSC32_OUT-Pad4)") (class "Default")
      (node (ref "STM32_1") (pin "4") (pinfunction "PC15-OSC32_OUT_4") (pintype "passive"))
    )
    (net (code "94") (name "unconnected-(USART4-Pad2)") (class "Default")
      (node (ref "USART4") (pin "2") (pinfunction "2_2") (pintype "passive"))
    )
    (net (code "95") (name "unconnected-(USART4-Pad3)") (class "Default")
      (node (ref "USART4") (pin "3") (pinfunction "3_3") (pintype "passive"))
    )
  )
)
